# Power.net
KiCad netlist of a schematic drawn in Altium Designer
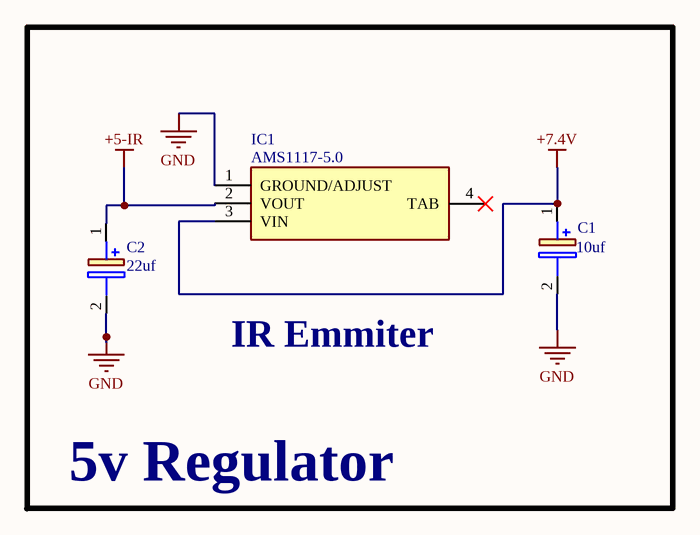
[diagram p0: Power.SchDoc]

(export (version "E")
  (design (tool "Eeschema 10.0.6"))
  (components
    (comp (ref "C1")
      (value "T491A106K006AT7280")
      (footprint "SamacSys:T491A")
      (description "Capacitor Polarised")
      (fields (field (name "MOUSER PART NUMBER") "80-T491A106K0067280") (field (name "CAPACITANCE") "10uf"))
      (libsource (lib "*") (part "T491A106K006AT7280"))
    )
    (comp (ref "C2")
      (value "F931C226MAAAJ6")
      (footprint "SamacSys:CAPPM3216X180N")
      (description "Capacitor Polarised")
      (fields (field (name "MOUSER PART NUMBER") "581-F931C226MAAAJ6") (field (name "CAPACITANCE") "22uf"))
      (libsource (lib "*") (part "F931C226MAAAJ6"))
    )
    (comp (ref "IC1")
      (value "AMS1117-5.0")
      (footprint "SamacSys:SOT229P700X180-4N")
      (description "Integrated Circuit")
      (libsource (lib "*") (part "AMS1117-5.0"))
    )
  )
  (nets
    (net (code "1") (name "+5-IR") (class "Default")
      (node (ref "C2") (pin "1") (pinfunction "+_1") (pintype "passive"))
      (node (ref "IC1") (pin "2") (pinfunction "VOUT_2") (pintype "passive"))
    )
    (net (code "2") (name "+7.4V") (class "Default")
      (node (ref "C1") (pin "1") (pinfunction "+_1") (pintype "passive"))
      (node (ref "IC1") (pin "3") (pinfunction "VIN_3") (pintype "passive"))
    )
    (net (code "3") (name "GND") (class "Default")
      (node (ref "C1") (pin "2") (pinfunction "-_2") (pintype "passive"))
      (node (ref "C2") (pin "2") (pinfunction "-_2") (pintype "passive"))
      (node (ref "IC1") (pin "1") (pinfunction "GROUND/ADJUST_1") (pintype "passive"))
    )
    (net (code "4") (name "unconnected-(IC1-TAB-Pad4)") (class "Default")
      (node (ref "IC1") (pin "4") (pinfunction "TAB_4") (pintype "passive+no_connect"))
    )
  )
)
